# uartjtag_block.net
KiCad netlist of a schematic drawn in Altium Designer
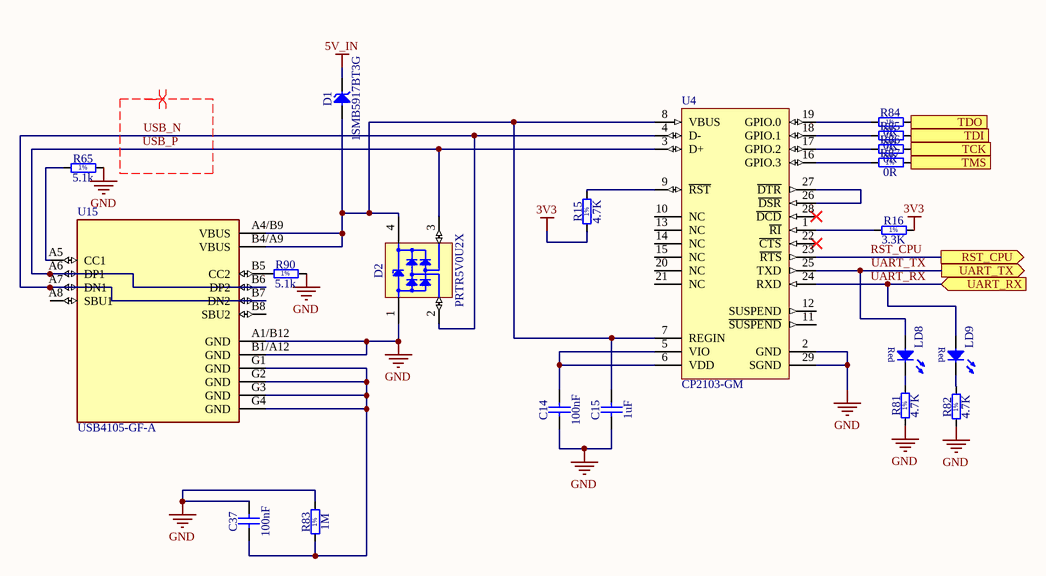
[diagram p0: uartjtag_block.SchDoc]

(export (version "E")
  (design (tool "Eeschema 10.0.6"))
  (components
    (comp (ref "C14")
      (value "100nF")
      (footprint "CAPC2013X100N")
      (description "Non-polarised capacitor")
      (fields
        (field (name "PART NUMBER") "CC0805_1.5NF_50V_5%_C0G")
        (field (name "VOLTAGE") "50V")
        (field (name "AUTHOR") "CERN DEM BC")
      )
      (libsource (lib "Capacitors") (part "Capacitor - non polarized"))
    )
    (comp (ref "C15")
      (value "1uF")
      (footprint "CAPC2013X100N")
      (description "Non-polarised capacitor")
      (fields
        (field (name "PART NUMBER") "CC0805_1.5NF_50V_5%_C0G")
        (field (name "VOLTAGE") "50V")
        (field (name "AUTHOR") "CERN DEM BC")
      )
      (libsource (lib "Capacitors") (part "Capacitor - non polarized"))
    )
    (comp (ref "C37")
      (value "100nF")
      (footprint "CAPC2013X100N")
      (description "Non-polarised capacitor")
      (fields
        (field (name "PART NUMBER") "CC0805_1.5NF_50V_5%_C0G")
        (field (name "VOLTAGE") "50V")
        (field (name "AUTHOR") "CERN DEM BC")
      )
      (libsource (lib "Capacitors") (part "Capacitor - non polarized"))
    )
    (comp (ref "D1")
      (value "1SMB5917BT3G")
      (footprint "DIOM5436X244N")
      (description "Zener Diode")
      (fields
        (field (name "VOLTAGE") "4.7V")
        (field (name "POWER") "3W")
        (field (name "AUTHOR") "CERN DEM MR")
      )
      (libsource (lib "ICs And Semiconductors") (part "Diode Zener"))
    )
    (comp (ref "D2")
      (value "PRTR5V0U2X")
      (footprint "SOT190P230X110-4N")
      (description "Ultra Low Capacitance Double Rail-to-Rail ESD Protection Diode")
      (fields
        (field (name "VOLTAGE") "5.5V")
        (field (name "MANUFACTURER") "NXP SEMICONDUCTORS")
        (field (name "AUTHOR") "CERN DEM JLC")
      )
      (libsource (lib "ICs And Semiconductors") (part "PRTR5V0U2X"))
    )
    (comp (ref "LD8")
      (value "Super Red")
      (footprint "LED_OSRAM_LSR976")
      (description "LED Red 1C 2A")
      (fields
        (field (name "PART NUMBER") "LED_OSRAM_LSR976")
        (field (name "MANUFACTURER") "OSRAM")
        (field (name "AUTHOR") "CERN DEM JLC")
      )
      (libsource (lib "ICs And Semiconductors") (part "LED Red 1C 2A"))
    )
    (comp (ref "LD9")
      (value "Super Red")
      (footprint "LED_OSRAM_LSR976")
      (description "LED Red 1C 2A")
      (fields
        (field (name "PART NUMBER") "LED_OSRAM_LSR976")
        (field (name "MANUFACTURER") "OSRAM")
        (field (name "AUTHOR") "CERN DEM JLC")
      )
      (libsource (lib "ICs And Semiconductors") (part "LED Red 1C 2A"))
    )
    (comp (ref "R15")
      (value "4.7K")
      (footprint "RESC1608X55N")
      (description "Resistor - 1%")
      (fields
        (field (name "PART NUMBER") "R0603_100K_1%_0.1W_100PPM")
        (field (name "POWER") "0.1W")
        (field (name "AUTHOR") "CERN DEM JLC")
      )
      (libsource (lib "Resistors") (part "Resistor - 1%"))
    )
    (comp (ref "R16")
      (value "3.3K")
      (footprint "RESC1608X55N")
      (description "Resistor - 1%")
      (fields
        (field (name "PART NUMBER") "R0603_100K_1%_0.1W_100PPM")
        (field (name "POWER") "0.1W")
        (field (name "AUTHOR") "CERN DEM JLC")
      )
      (libsource (lib "Resistors") (part "Resistor - 1%"))
    )
    (comp (ref "R65")
      (value "5.1k")
      (footprint "RESC1608X55N")
      (description "Resistor - 1%")
      (fields
        (field (name "PART NUMBER") "R0603_100K_1%_0.1W_100PPM")
        (field (name "POWER") "0.1W")
        (field (name "AUTHOR") "CERN DEM JLC")
      )
      (libsource (lib "Resistors") (part "Resistor - 1%"))
    )
    (comp (ref "R81")
      (value "4.7K")
      (footprint "RESC1608X55N")
      (description "Resistor - 1%")
      (fields
        (field (name "PART NUMBER") "R0603_100K_1%_0.1W_100PPM")
        (field (name "POWER") "0.1W")
        (field (name "AUTHOR") "CERN DEM JLC")
      )
      (libsource (lib "Resistors") (part "Resistor - 1%"))
    )
    (comp (ref "R82")
      (value "4.7K")
      (footprint "RESC1608X55N")
      (description "Resistor - 1%")
      (fields
        (field (name "PART NUMBER") "R0603_100K_1%_0.1W_100PPM")
        (field (name "POWER") "0.1W")
        (field (name "AUTHOR") "CERN DEM JLC")
      )
      (libsource (lib "Resistors") (part "Resistor - 1%"))
    )
    (comp (ref "R83")
      (value "1M")
      (footprint "RESC1608X55N")
      (description "Resistor - 1%")
      (fields
        (field (name "PART NUMBER") "R0603_100K_1%_0.1W_100PPM")
        (field (name "POWER") "0.1W")
        (field (name "AUTHOR") "CERN DEM JLC")
      )
      (libsource (lib "Resistors") (part "Resistor - 1%"))
    )
    (comp (ref "R84")
      (value "0R")
      (footprint "RESC1608X55N")
      (description "Resistor - 1%")
      (fields
        (field (name "PART NUMBER") "R0603_100K_1%_0.1W_100PPM")
        (field (name "POWER") "0.1W")
        (field (name "AUTHOR") "CERN DEM JLC")
      )
      (libsource (lib "Resistors") (part "Resistor - 1%"))
    )
    (comp (ref "R85")
      (value "0R")
      (footprint "RESC1608X55N")
      (description "Resistor - 1%")
      (fields
        (field (name "PART NUMBER") "R0603_100K_1%_0.1W_100PPM")
        (field (name "POWER") "0.1W")
        (field (name "AUTHOR") "CERN DEM JLC")
      )
      (libsource (lib "Resistors") (part "Resistor - 1%"))
    )
    (comp (ref "R86")
      (value "0R")
      (footprint "RESC1608X55N")
      (description "Resistor - 1%")
      (fields
        (field (name "PART NUMBER") "R0603_100K_1%_0.1W_100PPM")
        (field (name "POWER") "0.1W")
        (field (name "AUTHOR") "CERN DEM JLC")
      )
      (libsource (lib "Resistors") (part "Resistor - 1%"))
    )
    (comp (ref "R87")
      (value "0R")
      (footprint "RESC1608X55N")
      (description "Resistor - 1%")
      (fields
        (field (name "PART NUMBER") "R0603_100K_1%_0.1W_100PPM")
        (field (name "POWER") "0.1W")
        (field (name "AUTHOR") "CERN DEM JLC")
      )
      (libsource (lib "Resistors") (part "Resistor - 1%"))
    )
    (comp (ref "R90")
      (value "5.1k")
      (footprint "RESC1608X55N")
      (description "Resistor - 1%")
      (fields
        (field (name "PART NUMBER") "R0603_100K_1%_0.1W_100PPM")
        (field (name "POWER") "0.1W")
        (field (name "AUTHOR") "CERN DEM JLC")
      )
      (libsource (lib "Resistors") (part "Resistor - 1%"))
    )
    (comp (ref "U4")
      (value "CP2103-GM")
      (footprint "SLAB-QFN-28-3125x3125TP_A_L")
      (description "Single-Chip USB to UART Bridge, 1024 Bytes EEPROM, -40 to 85 degC, 28-pin QFN, Tube")
      (fields (field (name "MANUFACTURER") "Silicon Labs"))
      (libsource (lib "Silicon Labs Interface") (part "CP2103-GM"))
    )
    (comp (ref "U15")
      (value "USB4105-GF-A")
      (footprint "GCT_USB4105-GF-A")
      (fields (field (name "MF") "GCT"))
      (libsource (lib "SnapEDAsch") (part "USB4105-GF-A"))
    )
  )
  (nets
    (net (code "1") (name "/RST_CPU") (class "Default")
      (node (ref "U4") (pin "23") (pinfunction "~{RTS}_23") (pintype "output"))
    )
    (net (code "2") (name "/TCK") (class "Default")
      (node (ref "R86") (pin "2") (pinfunction "2_2") (pintype "passive"))
    )
    (net (code "3") (name "/TDI") (class "Default")
      (node (ref "R85") (pin "2") (pinfunction "2_2") (pintype "passive"))
    )
    (net (code "4") (name "/TDO") (class "Default")
      (node (ref "R84") (pin "2") (pinfunction "2_2") (pintype "passive"))
    )
    (net (code "5") (name "/TMS") (class "Default")
      (node (ref "R87") (pin "2") (pinfunction "2_2") (pintype "passive"))
    )
    (net (code "6") (name "/UART_RX") (class "Default")
      (node (ref "LD9") (pin "2") (pinfunction "A_2") (pintype "passive"))
      (node (ref "U4") (pin "24") (pinfunction "RXD_24") (pintype "input"))
    )
    (net (code "7") (name "/UART_TX") (class "Default")
      (node (ref "LD8") (pin "2") (pinfunction "A_2") (pintype "passive"))
      (node (ref "U4") (pin "25") (pinfunction "TXD_25") (pintype "output"))
    )
    (net (code "8") (name "/USB_N") (class "Default")
      (node (ref "D2") (pin "2") (pinfunction "I/O1_2") (pintype "bidirectional"))
      (node (ref "U15") (pin "A7") (pinfunction "DN1_A7") (pintype "bidirectional"))
      (node (ref "U15") (pin "B7") (pinfunction "DN2_B7") (pintype "bidirectional"))
      (node (ref "U4") (pin "4") (pinfunction "D-_4") (pintype "bidirectional"))
    )
    (net (code "9") (name "/USB_P") (class "Default")
      (node (ref "D2") (pin "3") (pinfunction "I/O2_3") (pintype "bidirectional"))
      (node (ref "U15") (pin "A6") (pinfunction "DP1_A6") (pintype "bidirectional"))
      (node (ref "U15") (pin "B6") (pinfunction "DP2_B6") (pintype "bidirectional"))
      (node (ref "U4") (pin "3") (pinfunction "D+_3") (pintype "bidirectional"))
    )
    (net (code "10") (name "3V3") (class "Default")
      (node (ref "R15") (pin "1") (pinfunction "1_1") (pintype "passive"))
      (node (ref "R16") (pin "2") (pinfunction "2_2") (pintype "passive"))
    )
    (net (code "11") (name "5V_IN") (class "Default")
      (node (ref "D1") (pin "1") (pinfunction "C_1") (pintype "passive"))
    )
    (net (code "12") (name "GND") (class "Default")
      (node (ref "C14") (pin "1") (pinfunction "1_1") (pintype "passive"))
      (node (ref "C15") (pin "1") (pinfunction "1_1") (pintype "passive"))
      (node (ref "C37") (pin "2") (pinfunction "2_2") (pintype "passive"))
      (node (ref "D2") (pin "1") (pinfunction "GND_1") (pintype "power_in"))
      (node (ref "R65") (pin "2") (pinfunction "2_2") (pintype "passive"))
      (node (ref "R81") (pin "1") (pinfunction "1_1") (pintype "passive"))
      (node (ref "R82") (pin "1") (pinfunction "1_1") (pintype "passive"))
      (node (ref "R83") (pin "2") (pinfunction "2_2") (pintype "passive"))
      (node (ref "R90") (pin "2") (pinfunction "2_2") (pintype "passive"))
      (node (ref "U15") (pin "A1/B12") (pinfunction "GND_A1/B12") (pintype "power_in"))
      (node (ref "U15") (pin "B1/A12") (pinfunction "GND_B1/A12") (pintype "power_in"))
      (node (ref "U4") (pin "2") (pinfunction "GND_2") (pintype "power_in"))
      (node (ref "U4") (pin "29") (pinfunction "SGND_29") (pintype "power_in"))
    )
    (net (code "13") (name "Net-(C37-Pad1)") (class "Default")
      (node (ref "C37") (pin "1") (pinfunction "1_1") (pintype "passive"))
      (node (ref "R83") (pin "1") (pinfunction "1_1") (pintype "passive"))
      (node (ref "U15") (pin "G1") (pinfunction "GND_G1") (pintype "power_in"))
      (node (ref "U15") (pin "G2") (pinfunction "GND_G2") (pintype "power_in"))
      (node (ref "U15") (pin "G3") (pinfunction "GND_G3") (pintype "power_in"))
      (node (ref "U15") (pin "G4") (pinfunction "GND_G4") (pintype "power_in"))
    )
    (net (code "14") (name "Net-(D1-A)") (class "Default")
      (node (ref "C15") (pin "2") (pinfunction "2_2") (pintype "passive"))
      (node (ref "D1") (pin "2") (pinfunction "A_2") (pintype "passive"))
      (node (ref "D2") (pin "4") (pinfunction "VCC_4") (pintype "power_in"))
      (node (ref "U15") (pin "A4/B9") (pinfunction "VBUS_A4/B9") (pintype "power_in"))
      (node (ref "U15") (pin "B4/A9") (pinfunction "VBUS_B4/A9") (pintype "power_in"))
      (node (ref "U4") (pin "7") (pinfunction "REGIN_7") (pintype "power_in"))
      (node (ref "U4") (pin "8") (pinfunction "VBUS_8") (pintype "input"))
    )
    (net (code "15") (name "Net-(LD8-C)") (class "Default")
      (node (ref "LD8") (pin "1") (pinfunction "C_1") (pintype "passive"))
      (node (ref "R81") (pin "2") (pinfunction "2_2") (pintype "passive"))
    )
    (net (code "16") (name "Net-(LD9-C)") (class "Default")
      (node (ref "LD9") (pin "1") (pinfunction "C_1") (pintype "passive"))
      (node (ref "R82") (pin "2") (pinfunction "2_2") (pintype "passive"))
    )
    (net (code "17") (name "Net-(U4-GPIO.0)") (class "Default")
      (node (ref "R84") (pin "1") (pinfunction "1_1") (pintype "passive"))
      (node (ref "U4") (pin "19") (pinfunction "GPIO.0_19") (pintype "bidirectional"))
    )
    (net (code "18") (name "Net-(U4-GPIO.1)") (class "Default")
      (node (ref "R85") (pin "1") (pinfunction "1_1") (pintype "passive"))
      (node (ref "U4") (pin "18") (pinfunction "GPIO.1_18") (pintype "bidirectional"))
    )
    (net (code "19") (name "Net-(U4-GPIO.2)") (class "Default")
      (node (ref "R86") (pin "1") (pinfunction "1_1") (pintype "passive"))
      (node (ref "U4") (pin "17") (pinfunction "GPIO.2_17") (pintype "bidirectional"))
    )
    (net (code "20") (name "Net-(U4-GPIO.3)") (class "Default")
      (node (ref "R87") (pin "1") (pinfunction "1_1") (pintype "passive"))
      (node (ref "U4") (pin "16") (pinfunction "GPIO.3_16") (pintype "bidirectional"))
    )
    (net (code "21") (name "Net-(U4-VDD)") (class "Default")
      (node (ref "C14") (pin "2") (pinfunction "2_2") (pintype "passive"))
      (node (ref "U4") (pin "5") (pinfunction "VIO_5") (pintype "power_in"))
      (node (ref "U4") (pin "6") (pinfunction "VDD_6") (pintype "power_in"))
    )
    (net (code "22") (name "Net-(U4-~{DSR})") (class "Default")
      (node (ref "U4") (pin "26") (pinfunction "~{DSR}_26") (pintype "input"))
      (node (ref "U4") (pin "27") (pinfunction "~{DTR}_27") (pintype "output"))
    )
    (net (code "23") (name "Net-(U4-~{RI})") (class "Default")
      (node (ref "R16") (pin "1") (pinfunction "1_1") (pintype "passive"))
      (node (ref "U4") (pin "1") (pinfunction "~{RI}_1") (pintype "input"))
    )
    (net (code "24") (name "Net-(U4-~{RST})") (class "Default")
      (node (ref "R15") (pin "2") (pinfunction "2_2") (pintype "passive"))
      (node (ref "U4") (pin "9") (pinfunction "~{RST}_9") (pintype "bidirectional"))
    )
    (net (code "25") (name "Net-(U15-CC1)") (class "Default")
      (node (ref "R65") (pin "1") (pinfunction "1_1") (pintype "passive"))
      (node (ref "U15") (pin "A5") (pinfunction "CC1_A5") (pintype "bidirectional"))
    )
    (net (code "26") (name "Net-(U15-CC2)") (class "Default")
      (node (ref "R90") (pin "1") (pinfunction "1_1") (pintype "passive"))
      (node (ref "U15") (pin "B5") (pinfunction "CC2_B5") (pintype "bidirectional"))
    )
    (net (code "27") (name "unconnected-(U4-NC-Pad10)") (class "Default")
      (node (ref "U4") (pin "10") (pinfunction "NC_10") (pintype "passive"))
    )
    (net (code "28") (name "unconnected-(U4-NC-Pad13)") (class "Default")
      (node (ref "U4") (pin "13") (pinfunction "NC_13") (pintype "passive"))
    )
    (net (code "29") (name "unconnected-(U4-NC-Pad14)") (class "Default")
      (node (ref "U4") (pin "14") (pinfunction "NC_14") (pintype "passive"))
    )
    (net (code "30") (name "unconnected-(U4-NC-Pad15)") (class "Default")
      (node (ref "U4") (pin "15") (pinfunction "NC_15") (pintype "passive"))
    )
    (net (code "31") (name "unconnected-(U4-NC-Pad20)") (class "Default")
      (node (ref "U4") (pin "20") (pinfunction "NC_20") (pintype "passive"))
    )
    (net (code "32") (name "unconnected-(U4-NC-Pad21)") (class "Default")
      (node (ref "U4") (pin "21") (pinfunction "NC_21") (pintype "passive"))
    )
    (net (code "33") (name "unconnected-(U4-SUSPEND-Pad12)") (class "Default")
      (node (ref "U4") (pin "12") (pinfunction "SUSPEND_12") (pintype "output"))
    )
    (net (code "34") (name "unconnected-(U4-~{CTS}-Pad22)") (class "Default")
      (node (ref "U4") (pin "22") (pinfunction "~{CTS}_22") (pintype "input+no_connect"))
    )
    (net (code "35") (name "unconnected-(U4-~{DCD}-Pad28)") (class "Default")
      (node (ref "U4") (pin "28") (pinfunction "~{DCD}_28") (pintype "input+no_connect"))
    )
    (net (code "36") (name "unconnected-(U4-~{SUSPEND}-Pad11)") (class "Default")
      (node (ref "U4") (pin "11") (pinfunction "~{SUSPEND}_11") (pintype "output"))
    )
    (net (code "37") (name "unconnected-(U15-SBU1-PadA8)") (class "Default")
      (node (ref "U15") (pin "A8") (pinfunction "SBU1_A8") (pintype "bidirectional"))
    )
    (net (code "38") (name "unconnected-(U15-SBU2-PadB8)") (class "Default")
      (node (ref "U15") (pin "B8") (pinfunction "SBU2_B8") (pintype "bidirectional"))
    )
  )
)
